# Maduino_Zero_Canbus_RS485_v2_0.net
KiCad netlist of a schematic drawn in EAGLE
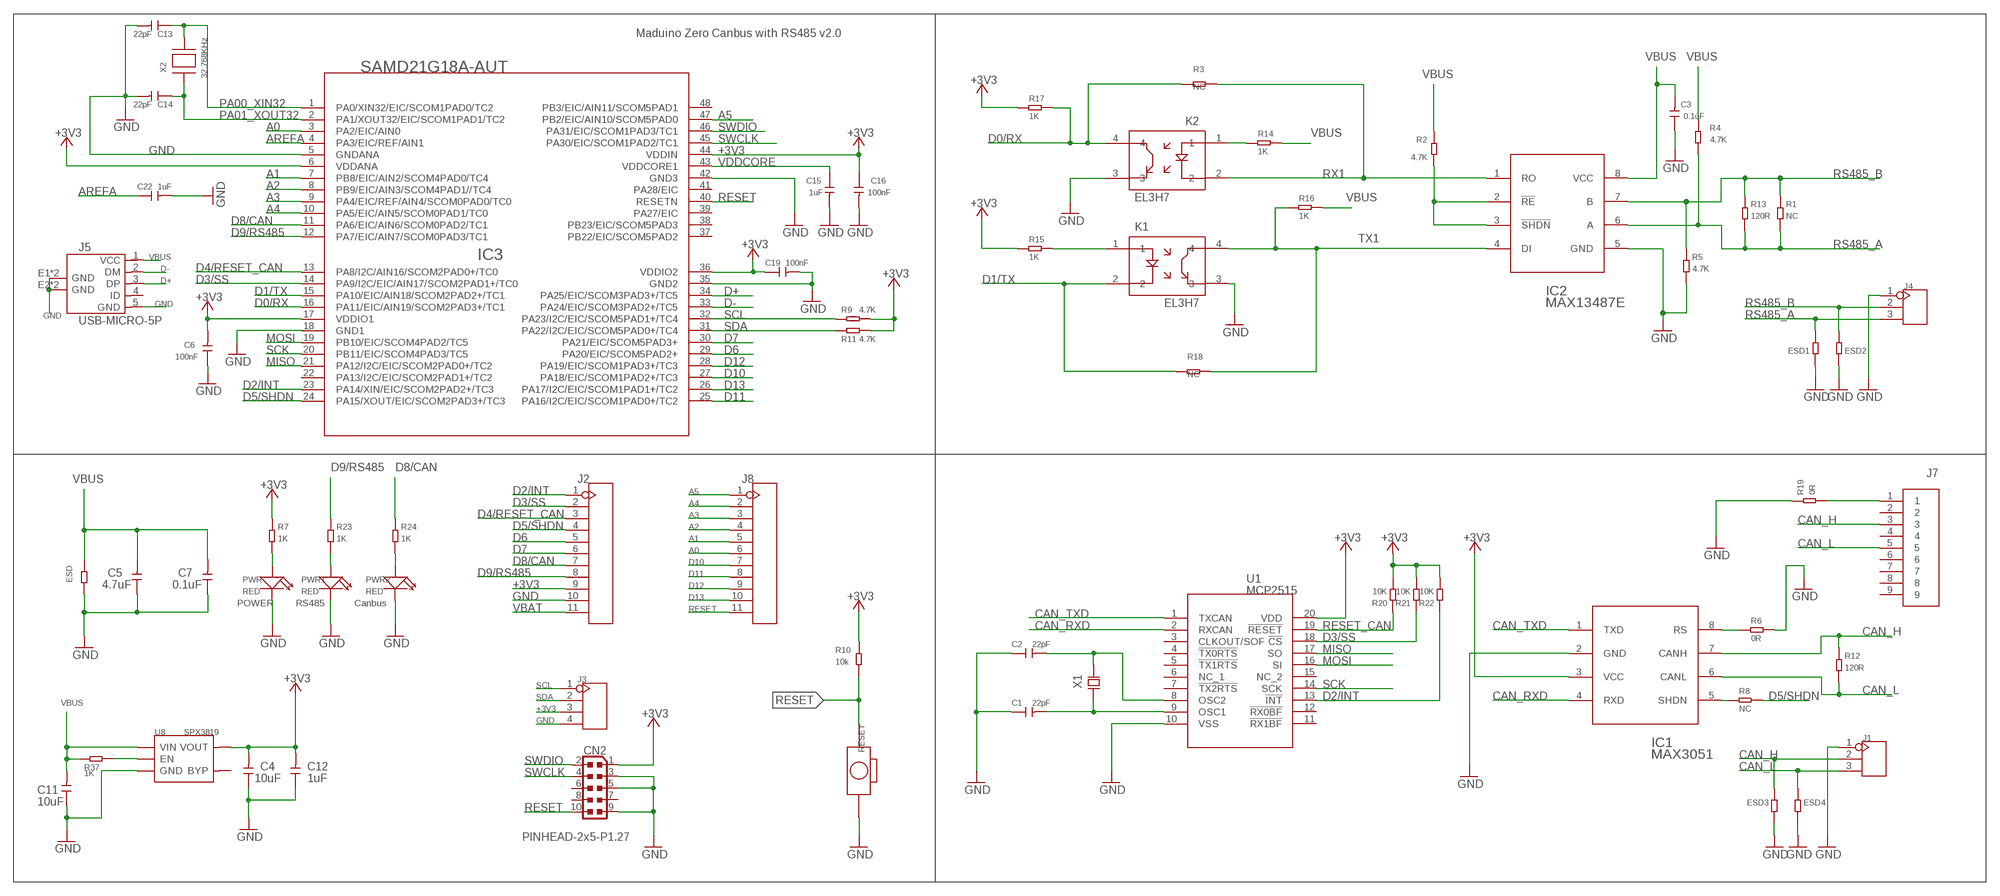
[diagram p0: schematic, sheet 1]

(export (version "E")
  (design (tool "Eeschema 10.0.6"))
  (components
    (comp (ref "C1")
      (value "22pF")
      (footprint "eagle-import:0603")
      (libsource (lib "eagle-import") (part "C-0603"))
    )
    (comp (ref "C2")
      (value "22pF")
      (footprint "eagle-import:0603")
      (libsource (lib "eagle-import") (part "C-0603"))
    )
    (comp (ref "C3")
      (value "0.1uF")
      (footprint "eagle-import:0603")
      (libsource (lib "eagle-import") (part "C-0603"))
    )
    (comp (ref "C4")
      (value "10uF")
      (footprint "eagle-import:0603")
      (libsource (lib "eagle-import") (part "C-0603"))
    )
    (comp (ref "C5")
      (value "4.7uF")
      (footprint "eagle-import:0603")
      (libsource (lib "eagle-import") (part "C-0603"))
    )
    (comp (ref "C6")
      (value "100nF")
      (footprint "eagle-import:0603")
      (libsource (lib "eagle-import") (part "C-0603"))
    )
    (comp (ref "C7")
      (value "0.1uF")
      (footprint "eagle-import:0603")
      (libsource (lib "eagle-import") (part "C-0603"))
    )
    (comp (ref "C11")
      (value "10uF")
      (footprint "eagle-import:0603")
      (libsource (lib "eagle-import") (part "C-0603"))
    )
    (comp (ref "C12")
      (value "1uF")
      (footprint "eagle-import:0603")
      (libsource (lib "eagle-import") (part "C-0603"))
    )
    (comp (ref "C13")
      (value "22pF")
      (footprint "eagle-import:0603")
      (libsource (lib "eagle-import") (part "C-0603"))
    )
    (comp (ref "C14")
      (value "22pF")
      (footprint "eagle-import:0603")
      (libsource (lib "eagle-import") (part "C-0603"))
    )
    (comp (ref "C15")
      (value "1uF")
      (footprint "eagle-import:0603")
      (libsource (lib "eagle-import") (part "C-0603"))
    )
    (comp (ref "C16")
      (value "100nF")
      (footprint "eagle-import:0603")
      (libsource (lib "eagle-import") (part "C-0603"))
    )
    (comp (ref "C19")
      (value "100nF")
      (footprint "eagle-import:0603")
      (libsource (lib "eagle-import") (part "C-0603"))
    )
    (comp (ref "C22")
      (value "1uF")
      (footprint "eagle-import:0603")
      (libsource (lib "eagle-import") (part "C-0603"))
    )
    (comp (ref "CN2")
      (value "PINHEAD-2x5-P1.27")
      (footprint "eagle-import:PINHEAD_2X05_127")
      (libsource (lib "eagle-import") (part "0171_PH127-205DF055G00AROUND-PADS"))
    )
    (comp (ref "ESD")
      (value "R-0603")
      (footprint "eagle-import:R0603")
      (libsource (lib "eagle-import") (part "R-0603"))
    )
    (comp (ref "ESD1")
      (value "R-0603")
      (footprint "eagle-import:R0603")
      (libsource (lib "eagle-import") (part "R-0603"))
    )
    (comp (ref "ESD2")
      (value "R-0603")
      (footprint "eagle-import:R0603")
      (libsource (lib "eagle-import") (part "R-0603"))
    )
    (comp (ref "ESD3")
      (value "NC")
      (footprint "eagle-import:R0603")
      (libsource (lib "eagle-import") (part "R-0603"))
    )
    (comp (ref "ESD4")
      (value "NC")
      (footprint "eagle-import:R0603")
      (libsource (lib "eagle-import") (part "R-0603"))
    )
    (comp (ref "IC1")
      (value "MAX3051")
      (footprint "eagle-import:DIP8_MX3051")
      (libsource (lib "eagle-import") (part "MAX3051"))
    )
    (comp (ref "IC2")
      (value "MAX13487E")
      (footprint "eagle-import:DIP8_MAX13487")
      (libsource (lib "eagle-import") (part "MAX13487E"))
    )
    (comp (ref "IC3")
      (value "SAMD21G18A-AUT")
      (footprint "eagle-import:TQFP48-7X7")
      (libsource (lib "eagle-import") (part "ATSAMD21G18A-AUT"))
    )
    (comp (ref "J1")
      (value "HEADER-3P-2.54")
      (footprint "eagle-import:3P-2.54")
      (libsource (lib "eagle-import") (part "HEADER-3P-2.54"))
    )
    (comp (ref "J2")
      (value "HEADER-11P-2.54")
      (footprint "eagle-import:11P-2.54")
      (libsource (lib "eagle-import") (part "HEADER-11P-2.54"))
    )
    (comp (ref "J3")
      (value "HEADER-4P-60/35MILROUND")
      (footprint "eagle-import:4P-65_35ROUND")
      (libsource (lib "eagle-import") (part "HEADER-4P-60/35MILROUND"))
    )
    (comp (ref "J4")
      (value "HEADER-3P-2.54")
      (footprint "eagle-import:3P-2.54")
      (libsource (lib "eagle-import") (part "HEADER-3P-2.54"))
    )
    (comp (ref "J5")
      (value "USB-MICRO-5P")
      (footprint "eagle-import:MICRO-USB-5P")
      (libsource (lib "eagle-import") (part "USB-MICRO-5P"))
    )
    (comp (ref "J7")
      (value "DB9-90")
      (footprint "eagle-import:DIP9-DB9-P2.77")
      (libsource (lib "eagle-import") (part "DB9-90"))
    )
    (comp (ref "J8")
      (value "HEADER-11P-2.54")
      (footprint "eagle-import:11P-2.54")
      (libsource (lib "eagle-import") (part "HEADER-11P-2.54"))
    )
    (comp (ref "K1")
      (value "EL3H7")
      (footprint "eagle-import:SOP-4_P1.27")
      (libsource (lib "eagle-import") (part "EL3H7"))
    )
    (comp (ref "K2")
      (value "EL3H7")
      (footprint "eagle-import:SOP-4_P1.27")
      (libsource (lib "eagle-import") (part "EL3H7"))
    )
    (comp (ref "PWR")
      (value "RED")
      (footprint "eagle-import:LED-0603")
      (libsource (lib "eagle-import") (part "LED'0603'"))
    )
    (comp (ref "PWR1")
      (value "RED")
      (footprint "eagle-import:LED-0603")
      (libsource (lib "eagle-import") (part "LED'0603'"))
    )
    (comp (ref "PWR2")
      (value "RED")
      (footprint "eagle-import:LED-0603")
      (libsource (lib "eagle-import") (part "LED'0603'"))
    )
    (comp (ref "R1")
      (value "NC")
      (footprint "eagle-import:R0603")
      (libsource (lib "eagle-import") (part "R-0603"))
    )
    (comp (ref "R2")
      (value "4.7K")
      (footprint "eagle-import:R0603")
      (libsource (lib "eagle-import") (part "R-0603"))
    )
    (comp (ref "R3")
      (value "NC")
      (footprint "eagle-import:R0603")
      (libsource (lib "eagle-import") (part "R-0603"))
    )
    (comp (ref "R4")
      (value "4.7K")
      (footprint "eagle-import:R0603")
      (libsource (lib "eagle-import") (part "R-0603"))
    )
    (comp (ref "R5")
      (value "4.7K")
      (footprint "eagle-import:R0603")
      (libsource (lib "eagle-import") (part "R-0603"))
    )
    (comp (ref "R6")
      (value "0R")
      (footprint "eagle-import:R0603")
      (libsource (lib "eagle-import") (part "R-0603"))
    )
    (comp (ref "R7")
      (value "1K")
      (footprint "eagle-import:R0603")
      (libsource (lib "eagle-import") (part "R-0603"))
    )
    (comp (ref "R8")
      (value "NC")
      (footprint "eagle-import:R0603")
      (libsource (lib "eagle-import") (part "R-0603"))
    )
    (comp (ref "R9")
      (value "4.7K")
      (footprint "eagle-import:R0603")
      (libsource (lib "eagle-import") (part "R-0603"))
    )
    (comp (ref "R10")
      (value "10k")
      (footprint "eagle-import:R0603")
      (libsource (lib "eagle-import") (part "R-0603"))
    )
    (comp (ref "R11")
      (value "4.7K")
      (footprint "eagle-import:R0603")
      (libsource (lib "eagle-import") (part "R-0603"))
    )
    (comp (ref "R12")
      (value "120R")
      (footprint "eagle-import:R0603")
      (libsource (lib "eagle-import") (part "R-0603"))
    )
    (comp (ref "R13")
      (value "120R")
      (footprint "eagle-import:R0603")
      (libsource (lib "eagle-import") (part "R-0603"))
    )
    (comp (ref "R14")
      (value "1K")
      (footprint "eagle-import:R0603")
      (libsource (lib "eagle-import") (part "R-0603"))
    )
    (comp (ref "R15")
      (value "1K")
      (footprint "eagle-import:R0603")
      (libsource (lib "eagle-import") (part "R-0603"))
    )
    (comp (ref "R16")
      (value "1K")
      (footprint "eagle-import:R0603")
      (libsource (lib "eagle-import") (part "R-0603"))
    )
    (comp (ref "R17")
      (value "1K")
      (footprint "eagle-import:R0603")
      (libsource (lib "eagle-import") (part "R-0603"))
    )
    (comp (ref "R18")
      (value "NC")
      (footprint "eagle-import:R0603")
      (libsource (lib "eagle-import") (part "R-0603"))
    )
    (comp (ref "R19")
      (value "0R")
      (footprint "eagle-import:R0603")
      (libsource (lib "eagle-import") (part "R-0603"))
    )
    (comp (ref "R20")
      (value "10K")
      (footprint "eagle-import:R0603")
      (libsource (lib "eagle-import") (part "R-0603"))
    )
    (comp (ref "R21")
      (value "10K")
      (footprint "eagle-import:R0603")
      (libsource (lib "eagle-import") (part "R-0603"))
    )
    (comp (ref "R22")
      (value "10K")
      (footprint "eagle-import:R0603")
      (libsource (lib "eagle-import") (part "R-0603"))
    )
    (comp (ref "R23")
      (value "1K")
      (footprint "eagle-import:R0603")
      (libsource (lib "eagle-import") (part "R-0603"))
    )
    (comp (ref "R24")
      (value "1K")
      (footprint "eagle-import:R0603")
      (libsource (lib "eagle-import") (part "R-0603"))
    )
    (comp (ref "R37")
      (value "1K")
      (footprint "eagle-import:R0603")
      (libsource (lib "eagle-import") (part "R-0603"))
    )
    (comp (ref "RESET")
      (value "BOTTON-2P-90D")
      (footprint "eagle-import:2P-7.62X3.56-90D")
      (libsource (lib "eagle-import") (part "BOTTON-2P-90D"))
    )
    (comp (ref "U1")
      (value "MCP2515")
      (footprint "eagle-import:SSOP-20")
      (libsource (lib "eagle-import") (part "MCP2515"))
    )
    (comp (ref "U8")
      (value "SPX3819")
      (footprint "eagle-import:SOT23-5")
      (libsource (lib "eagle-import") (part "SPX3819"))
    )
    (comp (ref "X1")
      (value "XTAL-8MHZ")
      (footprint "eagle-import:SMD-5032_2P_8M")
      (libsource (lib "eagle-import") (part "XTAL-8MHZ"))
    )
    (comp (ref "X2")
      (value "32.768KHz")
      (footprint "eagle-import:XTAL3215")
      (libsource (lib "eagle-import") (part "XTAL-3.2X1.5"))
    )
  )
  (nets
    (net (code "1") (name "+3V3") (class "Default")
      (node (ref "C12") (pin "2") (pinfunction "2_2") (pintype "passive"))
      (node (ref "C16") (pin "1") (pinfunction "1_1") (pintype "passive"))
      (node (ref "C19") (pin "1") (pinfunction "1_1") (pintype "passive"))
      (node (ref "C4") (pin "2") (pinfunction "2_2") (pintype "passive"))
      (node (ref "C6") (pin "2") (pinfunction "2_2") (pintype "passive"))
      (node (ref "CN2") (pin "1") (pinfunction "1_1") (pintype "passive"))
      (node (ref "IC1") (pin "3") (pinfunction "VCC_3") (pintype "bidirectional"))
      (node (ref "IC3") (pin "17") (pinfunction "VDDIO1_17") (pintype "power_in"))
      (node (ref "IC3") (pin "36") (pinfunction "VDDIO2_36") (pintype "power_in"))
      (node (ref "IC3") (pin "44") (pinfunction "VDDIN_44") (pintype "power_in"))
      (node (ref "IC3") (pin "6") (pinfunction "VDDANA_6") (pintype "power_in"))
      (node (ref "J2") (pin "9") (pinfunction "9_9") (pintype "bidirectional"))
      (node (ref "J3") (pin "3") (pinfunction "P$3_3") (pintype "bidirectional"))
      (node (ref "R10") (pin "2") (pinfunction "2_2") (pintype "passive"))
      (node (ref "R11") (pin "2") (pinfunction "2_2") (pintype "passive"))
      (node (ref "R15") (pin "2") (pinfunction "2_2") (pintype "passive"))
      (node (ref "R17") (pin "2") (pinfunction "2_2") (pintype "passive"))
      (node (ref "R20") (pin "1") (pinfunction "1_1") (pintype "passive"))
      (node (ref "R21") (pin "1") (pinfunction "1_1") (pintype "passive"))
      (node (ref "R22") (pin "1") (pinfunction "1_1") (pintype "passive"))
      (node (ref "R7") (pin "1") (pinfunction "1_1") (pintype "passive"))
      (node (ref "R9") (pin "2") (pinfunction "2_2") (pintype "passive"))
      (node (ref "U1") (pin "20") (pinfunction "VDD_20") (pintype "bidirectional"))
      (node (ref "U8") (pin "5") (pinfunction "VOUT_5") (pintype "bidirectional"))
    )
    (net (code "2") (name "/A0") (class "Default")
      (node (ref "IC3") (pin "3") (pinfunction "PA2/EIC/AIN0_3") (pintype "bidirectional"))
      (node (ref "J8") (pin "6") (pinfunction "6_6") (pintype "bidirectional"))
    )
    (net (code "3") (name "/A1") (class "Default")
      (node (ref "IC3") (pin "7") (pinfunction "PB8/EIC/AIN2/SCOM4PAD0/TC4_7") (pintype "bidirectional"))
      (node (ref "J8") (pin "5") (pinfunction "5_5") (pintype "bidirectional"))
    )
    (net (code "4") (name "/A2") (class "Default")
      (node (ref "IC3") (pin "8") (pinfunction "PB9/EIC/AIN3/SCOM4PAD1//TC4_8") (pintype "bidirectional"))
      (node (ref "J8") (pin "4") (pinfunction "4_4") (pintype "bidirectional"))
    )
    (net (code "5") (name "/A3") (class "Default")
      (node (ref "IC3") (pin "9") (pinfunction "PA4/EIC/REF/AIN4/SCOM0PAD0/TC0_9") (pintype "bidirectional"))
      (node (ref "J8") (pin "3") (pinfunction "3_3") (pintype "bidirectional"))
    )
    (net (code "6") (name "/A4") (class "Default")
      (node (ref "IC3") (pin "10") (pinfunction "PA5/EIC/AIN5/SCOM0PAD1/TC0_10") (pintype "bidirectional"))
      (node (ref "J8") (pin "2") (pinfunction "2_2") (pintype "bidirectional"))
    )
    (net (code "7") (name "/A5") (class "Default")
      (node (ref "IC3") (pin "47") (pinfunction "PB2/EIC/AIN10/SCOM5PAD0_47") (pintype "bidirectional"))
      (node (ref "J8") (pin "1") (pinfunction "1_1") (pintype "bidirectional"))
    )
    (net (code "8") (name "/AREFA") (class "Default")
      (node (ref "C22") (pin "1") (pinfunction "1_1") (pintype "passive"))
      (node (ref "IC3") (pin "4") (pinfunction "PA3/EIC/REF/AIN1_4") (pintype "bidirectional"))
    )
    (net (code "9") (name "/CAN_H") (class "Default")
      (node (ref "ESD3") (pin "1") (pinfunction "1_1") (pintype "passive"))
      (node (ref "IC1") (pin "7") (pinfunction "CANH_7") (pintype "bidirectional"))
      (node (ref "J1") (pin "2") (pinfunction "P$2_2") (pintype "bidirectional"))
      (node (ref "J7") (pin "3") (pinfunction "3_3") (pintype "bidirectional"))
      (node (ref "R12") (pin "1") (pinfunction "1_1") (pintype "passive"))
    )
    (net (code "10") (name "/CAN_L") (class "Default")
      (node (ref "ESD4") (pin "1") (pinfunction "1_1") (pintype "passive"))
      (node (ref "IC1") (pin "6") (pinfunction "CANL_6") (pintype "bidirectional"))
      (node (ref "J1") (pin "3") (pinfunction "P$3_3") (pintype "bidirectional"))
      (node (ref "J7") (pin "5") (pinfunction "5_5") (pintype "bidirectional"))
      (node (ref "R12") (pin "2") (pinfunction "2_2") (pintype "passive"))
    )
    (net (code "11") (name "/CAN_RXD") (class "Default")
      (node (ref "IC1") (pin "4") (pinfunction "RXD_4") (pintype "bidirectional"))
      (node (ref "U1") (pin "2") (pinfunction "RXCAN_2") (pintype "bidirectional"))
    )
    (net (code "12") (name "/CAN_TXD") (class "Default")
      (node (ref "IC1") (pin "1") (pinfunction "TXD_1") (pintype "bidirectional"))
      (node (ref "U1") (pin "1") (pinfunction "TXCAN_1") (pintype "bidirectional"))
    )
    (net (code "13") (name "/D+") (class "Default")
      (node (ref "IC3") (pin "34") (pinfunction "PA25/EIC/SCOM3PAD3+/TC5_34") (pintype "bidirectional"))
      (node (ref "J5") (pin "3") (pinfunction "DP_3") (pintype "bidirectional"))
    )
    (net (code "14") (name "/D-") (class "Default")
      (node (ref "IC3") (pin "33") (pinfunction "PA24/EIC/SCOM3PAD2+/TC5_33") (pintype "bidirectional"))
      (node (ref "J5") (pin "2") (pinfunction "DM_2") (pintype "bidirectional"))
    )
    (net (code "15") (name "/D0{slash}RX") (class "Default")
      (node (ref "IC3") (pin "16") (pinfunction "PA11/EIC/AIN19/SCOM2PAD3+/TC1_16") (pintype "bidirectional"))
      (node (ref "K2") (pin "4") (pinfunction "4_4") (pintype "bidirectional"))
      (node (ref "R17") (pin "1") (pinfunction "1_1") (pintype "passive"))
      (node (ref "R3") (pin "2") (pinfunction "2_2") (pintype "passive"))
    )
    (net (code "16") (name "/D1{slash}TX") (class "Default")
      (node (ref "IC3") (pin "15") (pinfunction "PA10/EIC/AIN18/SCOM2PAD2+/TC1_15") (pintype "bidirectional"))
      (node (ref "K1") (pin "2") (pinfunction "2_2") (pintype "bidirectional"))
      (node (ref "R18") (pin "2") (pinfunction "2_2") (pintype "passive"))
    )
    (net (code "17") (name "/D2{slash}INT") (class "Default")
      (node (ref "IC3") (pin "23") (pinfunction "PA14/XIN/EIC/SCOM2PAD2+/TC3_23") (pintype "bidirectional"))
      (node (ref "J2") (pin "1") (pinfunction "1_1") (pintype "bidirectional"))
      (node (ref "R22") (pin "2") (pinfunction "2_2") (pintype "passive"))
      (node (ref "U1") (pin "13") (pinfunction "~{INT}_13") (pintype "bidirectional"))
    )
    (net (code "18") (name "/D3{slash}SS") (class "Default")
      (node (ref "IC3") (pin "14") (pinfunction "PA9/I2C/EIC/AIN17/SCOM2PAD1+/TC0_14") (pintype "bidirectional"))
      (node (ref "J2") (pin "2") (pinfunction "2_2") (pintype "bidirectional"))
      (node (ref "R21") (pin "2") (pinfunction "2_2") (pintype "passive"))
      (node (ref "U1") (pin "18") (pinfunction "~{CS}_18") (pintype "bidirectional"))
    )
    (net (code "19") (name "/D4{slash}RESET_CAN") (class "Default")
      (node (ref "IC3") (pin "13") (pinfunction "PA8/I2C/AIN16/SCOM2PAD0+/TC0_13") (pintype "bidirectional"))
      (node (ref "J2") (pin "3") (pinfunction "3_3") (pintype "bidirectional"))
    )
    (net (code "20") (name "/D5{slash}SHDN") (class "Default")
      (node (ref "IC3") (pin "24") (pinfunction "PA15/XOUT/EIC/SCOM2PAD3+/TC3_24") (pintype "bidirectional"))
      (node (ref "J2") (pin "4") (pinfunction "4_4") (pintype "bidirectional"))
      (node (ref "R8") (pin "1") (pinfunction "1_1") (pintype "passive"))
    )
    (net (code "21") (name "/D6") (class "Default")
      (node (ref "IC3") (pin "29") (pinfunction "PA20/EIC/SCOM5PAD2+_29") (pintype "bidirectional"))
      (node (ref "J2") (pin "5") (pinfunction "5_5") (pintype "bidirectional"))
    )
    (net (code "22") (name "/D7") (class "Default")
      (node (ref "IC3") (pin "30") (pinfunction "PA21/EIC/SCOM5PAD3+_30") (pintype "bidirectional"))
      (node (ref "J2") (pin "6") (pinfunction "6_6") (pintype "bidirectional"))
    )
    (net (code "23") (name "/D8{slash}CAN") (class "Default")
      (node (ref "IC3") (pin "11") (pinfunction "PA6/EIC/AIN6/SCOM0PAD2/TC1_11") (pintype "bidirectional"))
      (node (ref "J2") (pin "7") (pinfunction "7_7") (pintype "bidirectional"))
      (node (ref "R24") (pin "1") (pinfunction "1_1") (pintype "passive"))
    )
    (net (code "24") (name "/D9{slash}RS485") (class "Default")
      (node (ref "IC3") (pin "12") (pinfunction "PA7/EIC/AIN7/SCOM0PAD3/TC1_12") (pintype "bidirectional"))
      (node (ref "J2") (pin "8") (pinfunction "8_8") (pintype "bidirectional"))
      (node (ref "R23") (pin "1") (pinfunction "1_1") (pintype "passive"))
    )
    (net (code "25") (name "/D10") (class "Default")
      (node (ref "IC3") (pin "27") (pinfunction "PA18/EIC/SCOM1PAD2+/TC3_27") (pintype "bidirectional"))
      (node (ref "J8") (pin "7") (pinfunction "7_7") (pintype "bidirectional"))
    )
    (net (code "26") (name "/D11") (class "Default")
      (node (ref "IC3") (pin "25") (pinfunction "PA16/I2C/EIC/SCOM1PAD0+/TC2_25") (pintype "bidirectional"))
      (node (ref "J8") (pin "8") (pinfunction "8_8") (pintype "bidirectional"))
    )
    (net (code "27") (name "/D12") (class "Default")
      (node (ref "IC3") (pin "28") (pinfunction "PA19/EIC/SCOM1PAD3+/TC3_28") (pintype "bidirectional"))
      (node (ref "J8") (pin "9") (pinfunction "9_9") (pintype "bidirectional"))
    )
    (net (code "28") (name "/D13") (class "Default")
      (node (ref "IC3") (pin "26") (pinfunction "PA17/I2C/EIC/SCOM1PAD1+/TC2_26") (pintype "bidirectional"))
      (node (ref "J8") (pin "10") (pinfunction "10_10") (pintype "bidirectional"))
    )
    (net (code "29") (name "/MISO") (class "Default")
      (node (ref "IC3") (pin "21") (pinfunction "PA12/I2C/EIC/SCOM2PAD0+/TC2_21") (pintype "bidirectional"))
      (node (ref "U1") (pin "17") (pinfunction "SO_17") (pintype "bidirectional"))
    )
    (net (code "30") (name "/MOSI") (class "Default")
      (node (ref "IC3") (pin "19") (pinfunction "PB10/EIC/SCOM4PAD2/TC5_19") (pintype "bidirectional"))
      (node (ref "U1") (pin "16") (pinfunction "SI_16") (pintype "bidirectional"))
    )
    (net (code "31") (name "/PA00_XIN32") (class "Default")
      (node (ref "C13") (pin "1") (pinfunction "1_1") (pintype "passive"))
      (node (ref "IC3") (pin "1") (pinfunction "PA0/XIN32/EIC/SCOM1PAD0/TC2_1") (pintype "bidirectional"))
      (node (ref "X2") (pin "P$2") (pinfunction "P$2_P$2") (pintype "bidirectional"))
    )
    (net (code "32") (name "/PA01_XOUT32") (class "Default")
      (node (ref "C14") (pin "1") (pinfunction "1_1") (pintype "passive"))
      (node (ref "IC3") (pin "2") (pinfunction "PA1/XOUT32/EIC/SCOM1PAD1/TC2_2") (pintype "bidirectional"))
      (node (ref "X2") (pin "P$1") (pinfunction "P$1_P$1") (pintype "bidirectional"))
    )
    (net (code "33") (name "/RESET_CAN") (class "Default")
      (node (ref "R20") (pin "2") (pinfunction "2_2") (pintype "passive"))
      (node (ref "U1") (pin "19") (pinfunction "~{RESET}_19") (pintype "bidirectional"))
    )
    (net (code "34") (name "/RS485_A") (class "Default")
      (node (ref "ESD1") (pin "2") (pinfunction "2_2") (pintype "passive"))
      (node (ref "IC2") (pin "6") (pinfunction "A_6") (pintype "bidirectional"))
      (node (ref "J4") (pin "3") (pinfunction "P$3_3") (pintype "bidirectional"))
      (node (ref "R1") (pin "1") (pinfunction "1_1") (pintype "passive"))
      (node (ref "R13") (pin "1") (pinfunction "1_1") (pintype "passive"))
      (node (ref "R4") (pin "1") (pinfunction "1_1") (pintype "passive"))
    )
    (net (code "35") (name "/RS485_B") (class "Default")
      (node (ref "ESD2") (pin "2") (pinfunction "2_2") (pintype "passive"))
      (node (ref "IC2") (pin "7") (pinfunction "B_7") (pintype "bidirectional"))
      (node (ref "J4") (pin "2") (pinfunction "P$2_2") (pintype "bidirectional"))
      (node (ref "R1") (pin "2") (pinfunction "2_2") (pintype "passive"))
      (node (ref "R13") (pin "2") (pinfunction "2_2") (pintype "passive"))
      (node (ref "R5") (pin "2") (pinfunction "2_2") (pintype "passive"))
    )
    (net (code "36") (name "/RX1") (class "Default")
      (node (ref "IC2") (pin "1") (pinfunction "RO_1") (pintype "bidirectional"))
      (node (ref "K2") (pin "2") (pinfunction "2_2") (pintype "bidirectional"))
      (node (ref "R3") (pin "1") (pinfunction "1_1") (pintype "passive"))
    )
    (net (code "37") (name "/SCK") (class "Default")
      (node (ref "IC3") (pin "20") (pinfunction "PB11/EIC/SCOM4PAD3/TC5_20") (pintype "bidirectional"))
      (node (ref "U1") (pin "14") (pinfunction "SCK_14") (pintype "bidirectional"))
    )
    (net (code "38") (name "/SCL") (class "Default")
      (node (ref "IC3") (pin "32") (pinfunction "PA23/I2C/EIC/SCOM5PAD1+/TC4_32") (pintype "bidirectional"))
      (node (ref "J3") (pin "1") (pinfunction "P$1_1") (pintype "bidirectional"))
      (node (ref "R9") (pin "1") (pinfunction "1_1") (pintype "passive"))
    )
    (net (code "39") (name "/SDA") (class "Default")
      (node (ref "IC3") (pin "31") (pinfunction "PA22/I2C/EIC/SCOM5PAD0+/TC4_31") (pintype "bidirectional"))
      (node (ref "J3") (pin "2") (pinfunction "P$2_2") (pintype "bidirectional"))
      (node (ref "R11") (pin "1") (pinfunction "1_1") (pintype "passive"))
    )
    (net (code "40") (name "/SWCLK") (class "Default")
      (node (ref "CN2") (pin "4") (pinfunction "4_4") (pintype "passive"))
      (node (ref "IC3") (pin "45") (pinfunction "PA30/EIC/SCOM1PAD2/TC1_45") (pintype "bidirectional"))
    )
    (net (code "41") (name "/SWDIO") (class "Default")
      (node (ref "CN2") (pin "2") (pinfunction "2_2") (pintype "passive"))
      (node (ref "IC3") (pin "46") (pinfunction "PA31/EIC/SCOM1PAD3/TC1_46") (pintype "bidirectional"))
    )
    (net (code "42") (name "/TX1") (class "Default")
      (node (ref "IC2") (pin "4") (pinfunction "DI_4") (pintype "bidirectional"))
      (node (ref "K1") (pin "4") (pinfunction "4_4") (pintype "bidirectional"))
      (node (ref "R16") (pin "2") (pinfunction "2_2") (pintype "passive"))
      (node (ref "R18") (pin "1") (pinfunction "1_1") (pintype "passive"))
    )
    (net (code "43") (name "/VBAT") (class "Default")
      (node (ref "J2") (pin "11") (pinfunction "11_11") (pintype "bidirectional"))
    )
    (net (code "44") (name "/VBUS") (class "Default")
      (node (ref "C11") (pin "2") (pinfunction "2_2") (pintype "passive"))
      (node (ref "C3") (pin "2") (pinfunction "2_2") (pintype "passive"))
      (node (ref "C5") (pin "2") (pinfunction "2_2") (pintype "passive"))
      (node (ref "C7") (pin "2") (pinfunction "2_2") (pintype "passive"))
      (node (ref "ESD") (pin "1") (pinfunction "1_1") (pintype "passive"))
      (node (ref "IC2") (pin "8") (pinfunction "VCC_8") (pintype "bidirectional"))
      (node (ref "J5") (pin "1") (pinfunction "VCC_1") (pintype "bidirectional"))
      (node (ref "R14") (pin "1") (pinfunction "1_1") (pintype "passive"))
      (node (ref "R16") (pin "1") (pinfunction "1_1") (pintype "passive"))
      (node (ref "R2") (pin "2") (pinfunction "2_2") (pintype "passive"))
      (node (ref "R37") (pin "1") (pinfunction "1_1") (pintype "passive"))
      (node (ref "R4") (pin "2") (pinfunction "2_2") (pintype "passive"))
      (node (ref "U8") (pin "1") (pinfunction "VIN_1") (pintype "bidirectional"))
    )
    (net (code "45") (name "/VDDCORE") (class "Default")
      (node (ref "C15") (pin "1") (pinfunction "1_1") (pintype "passive"))
      (node (ref "IC3") (pin "43") (pinfunction "VDDCORE1_43") (pintype "input"))
    )
    (net (code "46") (name "GND") (class "Default")
      (node (ref "C1") (pin "1") (pinfunction "1_1") (pintype "passive"))
      (node (ref "C11") (pin "1") (pinfunction "1_1") (pintype "passive"))
      (node (ref "C12") (pin "1") (pinfunction "1_1") (pintype "passive"))
      (node (ref "C13") (pin "2") (pinfunction "2_2") (pintype "passive"))
      (node (ref "C14") (pin "2") (pinfunction "2_2") (pintype "passive"))
      (node (ref "C15") (pin "2") (pinfunction "2_2") (pintype "passive"))
      (node (ref "C16") (pin "2") (pinfunction "2_2") (pintype "passive"))
      (node (ref "C19") (pin "2") (pinfunction "2_2") (pintype "passive"))
      (node (ref "C2") (pin "1") (pinfunction "1_1") (pintype "passive"))
      (node (ref "C22") (pin "2") (pinfunction "2_2") (pintype "passive"))
      (node (ref "C3") (pin "1") (pinfunction "1_1") (pintype "passive"))
      (node (ref "C4") (pin "1") (pinfunction "1_1") (pintype "passive"))
      (node (ref "C5") (pin "1") (pinfunction "1_1") (pintype "passive"))
      (node (ref "C6") (pin "1") (pinfunction "1_1") (pintype "passive"))
      (node (ref "C7") (pin "1") (pinfunction "1_1") (pintype "passive"))
      (node (ref "CN2") (pin "3") (pinfunction "3_3") (pintype "passive"))
      (node (ref "CN2") (pin "5") (pinfunction "5_5") (pintype "passive"))
      (node (ref "CN2") (pin "9") (pinfunction "9_9") (pintype "passive"))
      (node (ref "ESD") (pin "2") (pinfunction "2_2") (pintype "passive"))
      (node (ref "ESD1") (pin "1") (pinfunction "1_1") (pintype "passive"))
      (node (ref "ESD2") (pin "1") (pinfunction "1_1") (pintype "passive"))
      (node (ref "ESD3") (pin "2") (pinfunction "2_2") (pintype "passive"))
      (node (ref "ESD4") (pin "2") (pinfunction "2_2") (pintype "passive"))
      (node (ref "IC1") (pin "2") (pinfunction "GND_2") (pintype "bidirectional"))
      (node (ref "IC2") (pin "5") (pinfunction "GND_5") (pintype "bidirectional"))
      (node (ref "IC3") (pin "18") (pinfunction "GND1_18") (pintype "power_in"))
      (node (ref "IC3") (pin "35") (pinfunction "GND2_35") (pintype "power_in"))
      (node (ref "IC3") (pin "42") (pinfunction "GND3_42") (pintype "power_in"))
      (node (ref "IC3") (pin "5") (pinfunction "GNDANA_5") (pintype "power_in"))
      (node (ref "J1") (pin "1") (pinfunction "P$1_1") (pintype "bidirectional"))
      (node (ref "J2") (pin "10") (pinfunction "10_10") (pintype "bidirectional"))
      (node (ref "J3") (pin "4") (pinfunction "P$4_4") (pintype "bidirectional"))
      (node (ref "J4") (pin "1") (pinfunction "P$1_1") (pintype "bidirectional"))
      (node (ref "J5") (pin "5") (pinfunction "GND_5") (pintype "bidirectional"))
      (node (ref "J5") (pin "E1") (pinfunction "GND_E1") (pintype "bidirectional"))
      (node (ref "J5") (pin "E2") (pinfunction "GND_E2") (pintype "bidirectional"))
      (node (ref "J5") (pin "P1") (pinfunction "GND_P1") (pintype "bidirectional"))
      (node (ref "J5") (pin "P2") (pinfunction "GND_P2") (pintype "bidirectional"))
      (node (ref "K1") (pin "3") (pinfunction "3_3") (pintype "bidirectional"))
      (node (ref "K2") (pin "3") (pinfunction "3_3") (pintype "bidirectional"))
      (node (ref "PWR") (pin "-") (pinfunction "-_-") (pintype "passive"))
      (node (ref "PWR1") (pin "-") (pinfunction "-_-") (pintype "passive"))
      (node (ref "PWR2") (pin "-") (pinfunction "-_-") (pintype "passive"))
      (node (ref "R19") (pin "2") (pinfunction "2_2") (pintype "passive"))
      (node (ref "R5") (pin "1") (pinfunction "1_1") (pintype "passive"))
      (node (ref "R6") (pin "1") (pinfunction "1_1") (pintype "passive"))
      (node (ref "RESET") (pin "P$2") (pinfunction "2_P$2") (pintype "bidirectional"))
      (node (ref "U1") (pin "10") (pinfunction "VSS_10") (pintype "bidirectional"))
      (node (ref "U8") (pin "2") (pinfunction "GND_2") (pintype "bidirectional"))
    )
    (net (code "47") (name "Net-(IC1-RS)") (class "Default")
      (node (ref "IC1") (pin "8") (pinfunction "RS_8") (pintype "bidirectional"))
      (node (ref "R6") (pin "2") (pinfunction "2_2") (pintype "passive"))
    )
    (net (code "48") (name "Net-(IC1-SHDN)") (class "Default")
      (node (ref "IC1") (pin "5") (pinfunction "SHDN_5") (pintype "bidirectional"))
      (node (ref "R8") (pin "2") (pinfunction "2_2") (pintype "passive"))
    )
    (net (code "49") (name "Net-(IC2-~{RE})") (class "Default")
      (node (ref "IC2") (pin "2") (pinfunction "~{RE}_2") (pintype "bidirectional"))
      (node (ref "IC2") (pin "3") (pinfunction "~{SHDN}_3") (pintype "bidirectional"))
      (node (ref "R2") (pin "1") (pinfunction "1_1") (pintype "passive"))
    )
    (net (code "50") (name "Net-(J7-Pad1)") (class "Default")
      (node (ref "J7") (pin "1") (pinfunction "1_1") (pintype "bidirectional"))
      (node (ref "R19") (pin "1") (pinfunction "1_1") (pintype "passive"))
    )
    (net (code "51") (name "Net-(K1-Pad1)") (class "Default")
      (node (ref "K1") (pin "1") (pinfunction "1_1") (pintype "bidirectional"))
      (node (ref "R15") (pin "1") (pinfunction "1_1") (pintype "passive"))
    )
    (net (code "52") (name "Net-(K2-Pad1)") (class "Default")
      (node (ref "K2") (pin "1") (pinfunction "1_1") (pintype "bidirectional"))
      (node (ref "R14") (pin "2") (pinfunction "2_2") (pintype "passive"))
    )
    (net (code "53") (name "Net-(PWR-Pad+)") (class "Default")
      (node (ref "PWR") (pin "+") (pinfunction "+_+") (pintype "passive"))
      (node (ref "R7") (pin "2") (pinfunction "2_2") (pintype "passive"))
    )
    (net (code "54") (name "Net-(PWR1-Pad+)") (class "Default")
      (node (ref "PWR1") (pin "+") (pinfunction "+_+") (pintype "passive"))
      (node (ref "R23") (pin "2") (pinfunction "2_2") (pintype "passive"))
    )
    (net (code "55") (name "Net-(PWR2-Pad+)") (class "Default")
      (node (ref "PWR2") (pin "+") (pinfunction "+_+") (pintype "passive"))
      (node (ref "R24") (pin "2") (pinfunction "2_2") (pintype "passive"))
    )
    (net (code "56") (name "Net-(U1-OSC1)") (class "Default")
      (node (ref "C1") (pin "2") (pinfunction "2_2") (pintype "passive"))
      (node (ref "U1") (pin "9") (pinfunction "OSC1_9") (pintype "bidirectional"))
      (node (ref "X1") (pin "1") (pinfunction "1_1") (pintype "bidirectional"))
    )
    (net (code "57") (name "Net-(U1-OSC2)") (class "Default")
      (node (ref "C2") (pin "2") (pinfunction "2_2") (pintype "passive"))
      (node (ref "U1") (pin "8") (pinfunction "OSC2_8") (pintype "bidirectional"))
      (node (ref "X1") (pin "2") (pinfunction "2_2") (pintype "bidirectional"))
    )
    (net (code "58") (name "Net-(U8-EN)") (class "Default")
      (node (ref "R37") (pin "2") (pinfunction "2_2") (pintype "passive"))
      (node (ref "U8") (pin "3") (pinfunction "EN_3") (pintype "bidirectional"))
    )
    (net (code "59") (name "RESET") (class "Default")
      (node (ref "CN2") (pin "10") (pinfunction "10_10") (pintype "passive"))
      (node (ref "IC3") (pin "40") (pinfunction "RESETN_40") (pintype "bidirectional"))
      (node (ref "J8") (pin "11") (pinfunction "11_11") (pintype "bidirectional"))
      (node (ref "R10") (pin "1") (pinfunction "1_1") (pintype "passive"))
      (node (ref "RESET") (pin "P$1") (pinfunction "1_P$1") (pintype "bidirectional"))
    )
    (net (code "60") (name "unconnected-(CN2-Pad6)") (class "Default")
      (node (ref "CN2") (pin "6") (pinfunction "6_6") (pintype "passive"))
    )
    (net (code "61") (name "unconnected-(CN2-Pad7)") (class "Default")
      (node (ref "CN2") (pin "7") (pinfunction "7_7") (pintype "passive"))
    )
    (net (code "62") (name "unconnected-(CN2-Pad8)") (class "Default")
      (node (ref "CN2") (pin "8") (pinfunction "8_8") (pintype "passive"))
    )
    (net (code "63") (name "unconnected-(IC3-PA13{slash}I2C{slash}EIC{slash}SCOM2PAD1+{slash}TC2-Pad22)") (class "Default")
      (node (ref "IC3") (pin "22") (pinfunction "PA13/I2C/EIC/SCOM2PAD1+/TC2_22") (pintype "bidirectional"))
    )
    (net (code "64") (name "unconnected-(IC3-PA27{slash}EIC-Pad39)") (class "Default")
      (node (ref "IC3") (pin "39") (pinfunction "PA27/EIC_39") (pintype "bidirectional"))
    )
    (net (code "65") (name "unconnected-(IC3-PA28{slash}EIC-Pad41)") (class "Default")
      (node (ref "IC3") (pin "41") (pinfunction "PA28/EIC_41") (pintype "bidirectional"))
    )
    (net (code "66") (name "unconnected-(IC3-PB3{slash}EIC{slash}AIN11{slash}SCOM5PAD1-Pad48)") (class "Default")
      (node (ref "IC3") (pin "48") (pinfunction "PB3/EIC/AIN11/SCOM5PAD1_48") (pintype "bidirectional"))
    )
    (net (code "67") (name "unconnected-(IC3-PB22{slash}EIC{slash}SCOM5PAD2-Pad37)") (class "Default")
      (node (ref "IC3") (pin "37") (pinfunction "PB22/EIC/SCOM5PAD2_37") (pintype "bidirectional"))
    )
    (net (code "68") (name "unconnected-(IC3-PB23{slash}EIC{slash}SCOM5PAD3-Pad38)") (class "Default")
      (node (ref "IC3") (pin "38") (pinfunction "PB23/EIC/SCOM5PAD3_38") (pintype "bidirectional"))
    )
    (net (code "69") (name "unconnected-(J5-ID-Pad4)") (class "Default")
      (node (ref "J5") (pin "4") (pinfunction "ID_4") (pintype "bidirectional"))
    )
    (net (code "70") (name "unconnected-(J7-Pad2)") (class "Default")
      (node (ref "J7") (pin "2") (pinfunction "2_2") (pintype "bidirectional"))
    )
    (net (code "71") (name "unconnected-(J7-Pad4)") (class "Default")
      (node (ref "J7") (pin "4") (pinfunction "4_4") (pintype "bidirectional"))
    )
    (net (code "72") (name "unconnected-(J7-Pad6)") (class "Default")
      (node (ref "J7") (pin "6") (pinfunction "6_6") (pintype "bidirectional"))
    )
    (net (code "73") (name "unconnected-(J7-Pad7)") (class "Default")
      (node (ref "J7") (pin "7") (pinfunction "7_7") (pintype "bidirectional"))
    )
    (net (code "74") (name "unconnected-(J7-Pad8)") (class "Default")
      (node (ref "J7") (pin "8") (pinfunction "8_8") (pintype "bidirectional"))
    )
    (net (code "75") (name "unconnected-(J7-Pad9)") (class "Default")
      (node (ref "J7") (pin "9") (pinfunction "9_9") (pintype "bidirectional"))
    )
    (net (code "76") (name "unconnected-(U1-CLKOUT{slash}SOF-Pad3)") (class "Default")
      (node (ref "U1") (pin "3") (pinfunction "CLKOUT/SOF_3") (pintype "bidirectional"))
    )
    (net (code "77") (name "unconnected-(U1-NC_1-Pad6)") (class "Default")
      (node (ref "U1") (pin "6") (pinfunction "NC_1_6") (pintype "bidirectional"))
    )
    (net (code "78") (name "unconnected-(U1-NC_2-Pad15)") (class "Default")
      (node (ref "U1") (pin "15") (pinfunction "NC_2_15") (pintype "bidirectional"))
    )
    (net (code "79") (name "unconnected-(U1-~{RX0BF}-Pad12)") (class "Default")
      (node (ref "U1") (pin "12") (pinfunction "~{RX0BF}_12") (pintype "bidirectional"))
    )
    (net (code "80") (name "unconnected-(U1-~{RX1BF}-Pad11)") (class "Default")
      (node (ref "U1") (pin "11") (pinfunction "~{RX1BF}_11") (pintype "bidirectional"))
    )
    (net (code "81") (name "unconnected-(U1-~{TX0RTS}-Pad4)") (class "Default")
      (node (ref "U1") (pin "4") (pinfunction "~{TX0RTS}_4") (pintype "bidirectional"))
    )
    (net (code "82") (name "unconnected-(U1-~{TX1RTS}-Pad5)") (class "Default")
      (node (ref "U1") (pin "5") (pinfunction "~{TX1RTS}_5") (pintype "bidirectional"))
    )
    (net (code "83") (name "unconnected-(U1-~{TX2RTS}-Pad7)") (class "Default")
      (node (ref "U1") (pin "7") (pinfunction "~{TX2RTS}_7") (pintype "bidirectional"))
    )
    (net (code "84") (name "unconnected-(U8-BYP-Pad4)") (class "Default")
      (node (ref "U8") (pin "4") (pinfunction "BYP_4") (pintype "bidirectional"))
    )
  )
)
